# 24V_to_3V3_1A_switching_regulator.net
KiCad netlist of a schematic drawn in EAGLE
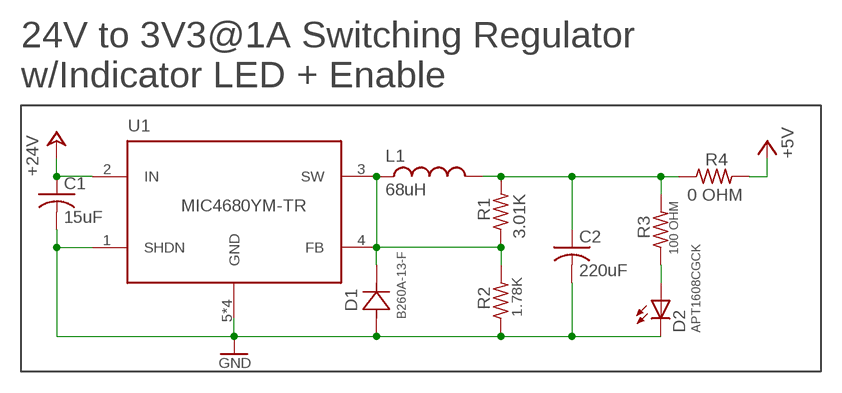
[diagram p0: schematic, sheet 1]

(export (version "E")
  (design (tool "Eeschema 10.0.6"))
  (components
    (comp (ref "C1")
      (value "15uF")
      (footprint "eagle-import:CT7343")
      (libsource (lib "eagle-import") (part "15UF-TPSD156K035R0100"))
    )
    (comp (ref "C2")
      (value "220uF")
      (footprint "eagle-import:CT7343")
      (libsource (lib "eagle-import") (part "220UF-TPSY227K010R0100"))
    )
    (comp (ref "D1")
      (value "B260A-13-F")
      (footprint "eagle-import:SMA")
      (libsource (lib "eagle-import") (part "B260A-13-F"))
    )
    (comp (ref "D2")
      (value "APT1608CGCK")
      (footprint "eagle-import:CHIPLED_0603")
      (libsource (lib "eagle-import") (part "APT1608CGCK"))
    )
    (comp (ref "L1")
      (value "68uH")
      (footprint "eagle-import:UP2B")
      (libsource (lib "eagle-import") (part "68UH-UP2B-680-R"))
    )
    (comp (ref "R1")
      (value "3.01K")
      (footprint "eagle-import:RC0603N")
      (libsource (lib "eagle-import") (part "3.01K-RC0603FR-073K01L"))
    )
    (comp (ref "R2")
      (value "1.78K")
      (footprint "eagle-import:RC0603N")
      (libsource (lib "eagle-import") (part "1.78K-RC0603FR-071K78L"))
    )
    (comp (ref "R3")
      (value "100 OHM")
      (footprint "eagle-import:RC0603N")
      (libsource (lib "eagle-import") (part "100OHM-RC0603JR-07100RL"))
    )
    (comp (ref "R4")
      (value "0 OHM")
      (footprint "eagle-import:RC0603N")
      (libsource (lib "eagle-import") (part "0OHM-RC0603JR-070RL"))
    )
    (comp (ref "U1")
      (value "MIC4680YM-TR")
      (footprint "eagle-import:SOIC8")
      (libsource (lib "eagle-import") (part "MIC4680YM-TR"))
    )
  )
  (nets
    (net (code "1") (name "+5V") (class "Default")
      (node (ref "R4") (pin "2") (pinfunction "2_2") (pintype "passive"))
    )
    (net (code "2") (name "+24V") (class "Default")
      (node (ref "C1") (pin "+") (pinfunction "1(+)_+") (pintype "passive"))
      (node (ref "U1") (pin "2") (pinfunction "IN_2") (pintype "bidirectional"))
    )
    (net (code "3") (name "GND") (class "Default")
      (node (ref "C1") (pin "-") (pinfunction "2(-)_-") (pintype "passive"))
      (node (ref "C2") (pin "-") (pinfunction "2(-)_-") (pintype "passive"))
      (node (ref "D1") (pin "2") (pinfunction "21_2") (pintype "passive"))
      (node (ref "D2") (pin "C") (pinfunction "C_C") (pintype "passive"))
      (node (ref "R2") (pin "1") (pinfunction "1_1") (pintype "passive"))
      (node (ref "U1") (pin "1") (pinfunction "SHDN_1") (pintype "bidirectional"))
      (node (ref "U1") (pin "5") (pinfunction "GND_5") (pintype "bidirectional"))
      (node (ref "U1") (pin "6") (pinfunction "GND_6") (pintype "bidirectional"))
      (node (ref "U1") (pin "7") (pinfunction "GND_7") (pintype "bidirectional"))
      (node (ref "U1") (pin "8") (pinfunction "GND_8") (pintype "bidirectional"))
    )
    (net (code "4") (name "Net-(C2-1(+))") (class "Default")
      (node (ref "C2") (pin "+") (pinfunction "1(+)_+") (pintype "passive"))
      (node (ref "L1") (pin "2") (pinfunction "2_2") (pintype "passive"))
      (node (ref "R1") (pin "2") (pinfunction "2_2") (pintype "passive"))
      (node (ref "R3") (pin "2") (pinfunction "2_2") (pintype "passive"))
      (node (ref "R4") (pin "1") (pinfunction "1_1") (pintype "passive"))
    )
    (net (code "5") (name "Net-(D1-12)") (class "Default")
      (node (ref "D1") (pin "1") (pinfunction "12_1") (pintype "passive"))
      (node (ref "L1") (pin "1") (pinfunction "1_1") (pintype "passive"))
      (node (ref "R1") (pin "1") (pinfunction "1_1") (pintype "passive"))
      (node (ref "R2") (pin "2") (pinfunction "2_2") (pintype "passive"))
      (node (ref "U1") (pin "3") (pinfunction "SW_3") (pintype "bidirectional"))
      (node (ref "U1") (pin "4") (pinfunction "FB_4") (pintype "bidirectional"))
    )
    (net (code "6") (name "Net-(D2-PadA)") (class "Default")
      (node (ref "D2") (pin "A") (pinfunction "A_A") (pintype "passive"))
      (node (ref "R3") (pin "1") (pinfunction "1_1") (pintype "passive"))
    )
  )
)
